# w076oAsBuilt.net
KiCad netlist of a schematic drawn in EAGLE
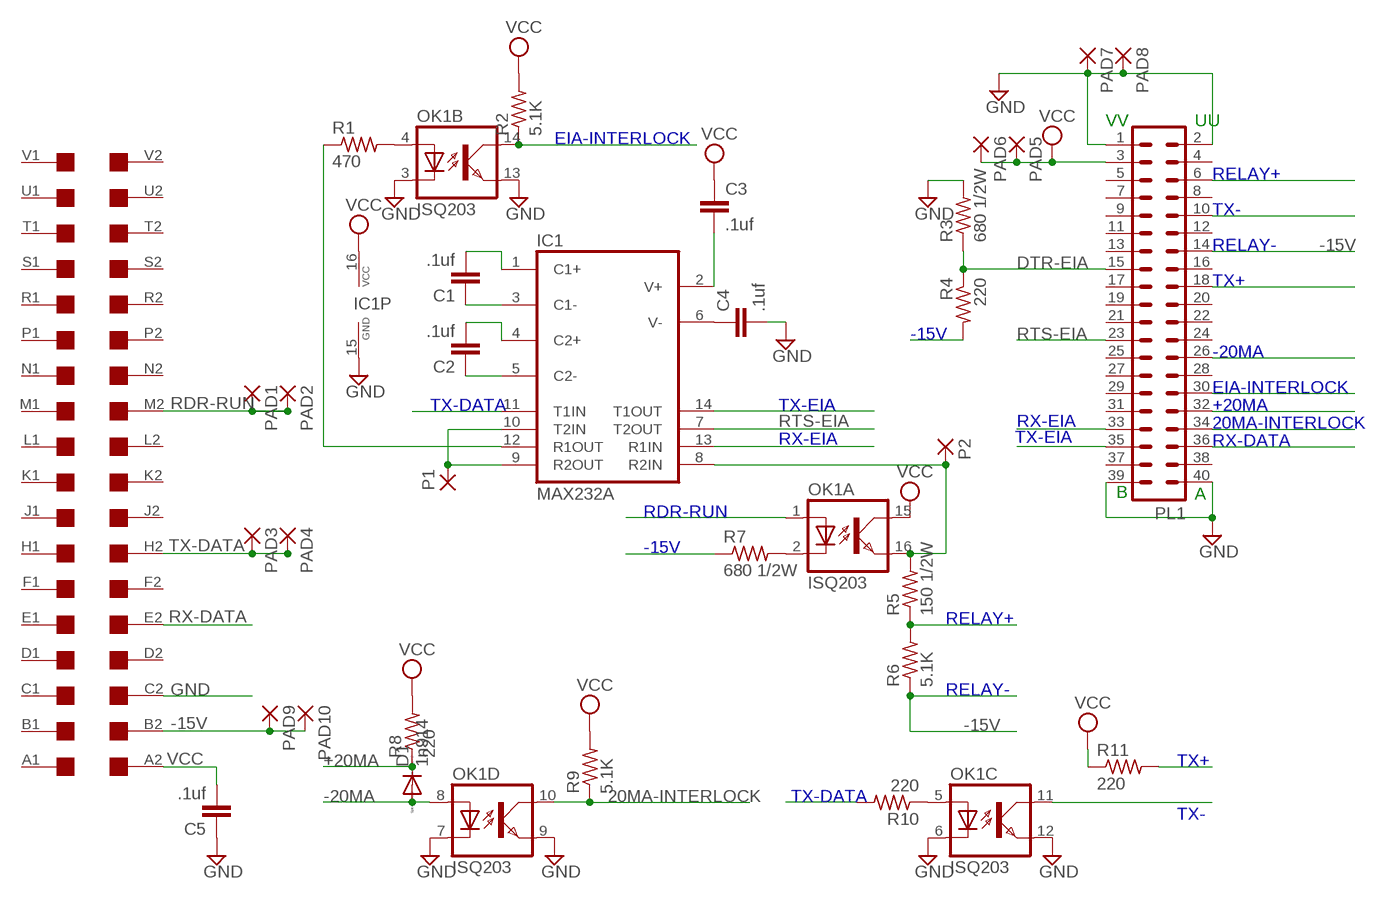
[diagram p0: schematic, sheet 1]

(export (version "E")
  (design (tool "Eeschema 10.0.6"))
  (components
    (comp (ref "C1")
      (value ".1uf")
      (footprint "eagle-import:C050-025X075")
      (libsource (lib "eagle-import") (part "C-EU050-025X075"))
    )
    (comp (ref "C2")
      (value ".1uf")
      (footprint "eagle-import:C050-025X075")
      (libsource (lib "eagle-import") (part "C-EU050-025X075"))
    )
    (comp (ref "C3")
      (value ".1uf")
      (footprint "eagle-import:C050-025X075")
      (libsource (lib "eagle-import") (part "C-EU050-025X075"))
    )
    (comp (ref "C4")
      (value ".1uf")
      (footprint "eagle-import:C050-025X075")
      (libsource (lib "eagle-import") (part "C-EU050-025X075"))
    )
    (comp (ref "C5")
      (value ".1uf")
      (footprint "eagle-import:C050-025X075")
      (libsource (lib "eagle-import") (part "C-EU050-025X075"))
    )
    (comp (ref "D1")
      (value "1n914")
      (footprint "eagle-import:DO41-10")
      (libsource (lib "eagle-import") (part "1N4004"))
    )
    (comp (ref "IC1")
      (value "MAX232A")
      (footprint "eagle-import:DIL16")
      (fields (field (name "MF") "MAXIM") (field (name "MPN") "MAX232ACPE+"))
      (libsource (lib "eagle-import") (part "MAX232"))
    )
    (comp (ref "OK1")
      (value "ISQ203")
      (footprint "eagle-import:DIL16")
      (fields (field (name "MF") "VISHAY/TELEFUNKEN") (field (name "MPN") "ILQ1"))
      (libsource (lib "eagle-import") (part "ILQ1"))
    )
    (comp (ref "P1")
      (value "1,6/0,8")
      (footprint "eagle-import:1,6_0,8")
      (libsource (lib "eagle-import") (part "1,6/0,8"))
    )
    (comp (ref "P2")
      (value "1,6/0,8")
      (footprint "eagle-import:1,6_0,8")
      (libsource (lib "eagle-import") (part "1,6/0,8"))
    )
    (comp (ref "PAD1")
      (value "1,6/0,8")
      (footprint "eagle-import:1,6_0,8")
      (libsource (lib "eagle-import") (part "1,6/0,8"))
    )
    (comp (ref "PAD2")
      (value "1,6/0,8")
      (footprint "eagle-import:1,6_0,8")
      (libsource (lib "eagle-import") (part "1,6/0,8"))
    )
    (comp (ref "PAD3")
      (value "1,6/0,8")
      (footprint "eagle-import:1,6_0,8")
      (libsource (lib "eagle-import") (part "1,6/0,8"))
    )
    (comp (ref "PAD4")
      (value "1,6/0,8")
      (footprint "eagle-import:1,6_0,8")
      (libsource (lib "eagle-import") (part "1,6/0,8"))
    )
    (comp (ref "PAD5")
      (value "1,6/0,8")
      (footprint "eagle-import:1,6_0,8")
      (libsource (lib "eagle-import") (part "1,6/0,8"))
    )
    (comp (ref "PAD6")
      (value "1,6/0,8")
      (footprint "eagle-import:1,6_0,8")
      (libsource (lib "eagle-import") (part "1,6/0,8"))
    )
    (comp (ref "PAD7")
      (value "1,6/0,8")
      (footprint "eagle-import:1,6_0,8")
      (libsource (lib "eagle-import") (part "1,6/0,8"))
    )
    (comp (ref "PAD8")
      (value "1,6/0,8")
      (footprint "eagle-import:1,6_0,8")
      (libsource (lib "eagle-import") (part "1,6/0,8"))
    )
    (comp (ref "PAD9")
      (value "1,6/0,8")
      (footprint "eagle-import:1,6_0,8")
      (libsource (lib "eagle-import") (part "1,6/0,8"))
    )
    (comp (ref "PAD10")
      (value "1,6/0,8")
      (footprint "eagle-import:1,6_0,8")
      (libsource (lib "eagle-import") (part "1,6/0,8"))
    )
    (comp (ref "PL1")
      (value "40H")
      (footprint "eagle-import:40H")
      (libsource (lib "eagle-import") (part "40H"))
    )
    (comp (ref "R1")
      (value "470")
      (footprint "eagle-import:0207_10")
      (libsource (lib "eagle-import") (part "R-US_0207/10"))
    )
    (comp (ref "R2")
      (value "5.1K")
      (footprint "eagle-import:0207_10")
      (libsource (lib "eagle-import") (part "R-US_0207/10"))
    )
    (comp (ref "R3")
      (value "680 1/2W")
      (footprint "eagle-import:0207_12")
      (libsource (lib "eagle-import") (part "R-US_0207/12"))
    )
    (comp (ref "R4")
      (value "220")
      (footprint "eagle-import:0207_10")
      (libsource (lib "eagle-import") (part "R-US_0207/10"))
    )
    (comp (ref "R5")
      (value "150 1/2W")
      (footprint "eagle-import:0207_12")
      (libsource (lib "eagle-import") (part "R-US_0207/12"))
    )
    (comp (ref "R6")
      (value "5.1K")
      (footprint "eagle-import:0207_10")
      (libsource (lib "eagle-import") (part "R-US_0207/10"))
    )
    (comp (ref "R7")
      (value "680 1/2W")
      (footprint "eagle-import:0207_12")
      (libsource (lib "eagle-import") (part "R-US_0207/12"))
    )
    (comp (ref "R8")
      (value "220")
      (footprint "eagle-import:0207_10")
      (libsource (lib "eagle-import") (part "R-US_0207/10"))
    )
    (comp (ref "R9")
      (value "5.1K")
      (footprint "eagle-import:0207_10")
      (libsource (lib "eagle-import") (part "R-US_0207/10"))
    )
    (comp (ref "R10")
      (value "220")
      (footprint "eagle-import:0207_10")
      (libsource (lib "eagle-import") (part "R-US_0207/10"))
    )
    (comp (ref "R11")
      (value "220")
      (footprint "eagle-import:0207_10")
      (libsource (lib "eagle-import") (part "R-US_0207/10"))
    )
    (comp (ref "U$1")
      (value "DEC-FLIPCHIP")
      (footprint "eagle-import:DEC-FLIPCHIP")
      (libsource (lib "eagle-import") (part "DEC-FLIPCHIP"))
    )
  )
  (nets
    (net (code "1") (name "/+20MA") (class "Default")
      (node (ref "D1") (pin "C") (pinfunction "C_C") (pintype "passive"))
      (node (ref "PL1") (pin "32") (pinfunction "32_32") (pintype "passive"))
      (node (ref "R8") (pin "1") (pinfunction "1_1") (pintype "passive"))
    )
    (net (code "2") (name "/-15V") (class "Default")
      (node (ref "PAD10") (pin "1") (pinfunction "P_1") (pintype "passive"))
      (node (ref "PAD9") (pin "1") (pinfunction "P_1") (pintype "passive"))
      (node (ref "PL1") (pin "14") (pinfunction "14_14") (pintype "passive"))
      (node (ref "R4") (pin "2") (pinfunction "2_2") (pintype "passive"))
      (node (ref "R6") (pin "1") (pinfunction "1_1") (pintype "passive"))
      (node (ref "R7") (pin "1") (pinfunction "1_1") (pintype "passive"))
      (node (ref "U$1") (pin "B2") (pinfunction "B2_B2") (pintype "passive"))
    )
    (net (code "3") (name "/-20MA") (class "Default")
      (node (ref "D1") (pin "A") (pinfunction "A_A") (pintype "passive"))
      (node (ref "OK1") (pin "8") (pinfunction "A_8") (pintype "passive"))
      (node (ref "PL1") (pin "26") (pinfunction "26_26") (pintype "passive"))
    )
    (net (code "4") (name "/20MA-INTERLOCK") (class "Default")
      (node (ref "OK1") (pin "10") (pinfunction "COL_10") (pintype "passive"))
      (node (ref "PL1") (pin "34") (pinfunction "34_34") (pintype "passive"))
      (node (ref "R9") (pin "1") (pinfunction "1_1") (pintype "passive"))
    )
    (net (code "5") (name "/DTR-EIA") (class "Default")
      (node (ref "PL1") (pin "15") (pinfunction "15_15") (pintype "passive"))
      (node (ref "R3") (pin "1") (pinfunction "1_1") (pintype "passive"))
      (node (ref "R4") (pin "1") (pinfunction "1_1") (pintype "passive"))
    )
    (net (code "6") (name "/EIA-INTERLOCK") (class "Default")
      (node (ref "OK1") (pin "14") (pinfunction "COL_14") (pintype "passive"))
      (node (ref "PL1") (pin "30") (pinfunction "30_30") (pintype "passive"))
      (node (ref "R2") (pin "1") (pinfunction "1_1") (pintype "passive"))
    )
    (net (code "7") (name "/RDR-RUN") (class "Default")
      (node (ref "OK1") (pin "1") (pinfunction "A_1") (pintype "passive"))
      (node (ref "PAD1") (pin "1") (pinfunction "P_1") (pintype "passive"))
      (node (ref "PAD2") (pin "1") (pinfunction "P_1") (pintype "passive"))
      (node (ref "U$1") (pin "M2") (pinfunction "M2_M2") (pintype "passive"))
    )
    (net (code "8") (name "/RELAY+") (class "Default")
      (node (ref "PL1") (pin "6") (pinfunction "6_6") (pintype "passive"))
      (node (ref "R5") (pin "1") (pinfunction "1_1") (pintype "passive"))
      (node (ref "R6") (pin "2") (pinfunction "2_2") (pintype "passive"))
    )
    (net (code "9") (name "/RTS-EIA") (class "Default")
      (node (ref "IC1") (pin "7") (pinfunction "T2OUT_7") (pintype "output"))
      (node (ref "PL1") (pin "23") (pinfunction "23_23") (pintype "passive"))
    )
    (net (code "10") (name "/RX-DATA") (class "Default")
      (node (ref "PL1") (pin "36") (pinfunction "36_36") (pintype "passive"))
      (node (ref "U$1") (pin "E2") (pinfunction "E2_E2") (pintype "passive"))
    )
    (net (code "11") (name "/RX-EIA") (class "Default")
      (node (ref "IC1") (pin "13") (pinfunction "R1IN_13") (pintype "input"))
      (node (ref "PL1") (pin "33") (pinfunction "33_33") (pintype "passive"))
    )
    (net (code "12") (name "/TX+") (class "Default")
      (node (ref "PL1") (pin "18") (pinfunction "18_18") (pintype "passive"))
      (node (ref "R11") (pin "2") (pinfunction "2_2") (pintype "passive"))
    )
    (net (code "13") (name "/TX-") (class "Default")
      (node (ref "OK1") (pin "11") (pinfunction "COL_11") (pintype "passive"))
      (node (ref "PL1") (pin "10") (pinfunction "10_10") (pintype "passive"))
    )
    (net (code "14") (name "/TX-DATA") (class "Default")
      (node (ref "IC1") (pin "11") (pinfunction "T1IN_11") (pintype "input"))
      (node (ref "PAD3") (pin "1") (pinfunction "P_1") (pintype "passive"))
      (node (ref "PAD4") (pin "1") (pinfunction "P_1") (pintype "passive"))
      (node (ref "R10") (pin "2") (pinfunction "2_2") (pintype "passive"))
      (node (ref "U$1") (pin "H2") (pinfunction "H2_H2") (pintype "passive"))
    )
    (net (code "15") (name "/TX-EIA") (class "Default")
      (node (ref "IC1") (pin "14") (pinfunction "T1OUT_14") (pintype "output"))
      (node (ref "PL1") (pin "35") (pinfunction "35_35") (pintype "passive"))
    )
    (net (code "16") (name "GND") (class "Default")
      (node (ref "C4") (pin "2") (pinfunction "2_2") (pintype "passive"))
      (node (ref "C5") (pin "1") (pinfunction "1_1") (pintype "passive"))
      (node (ref "IC1") (pin "15") (pinfunction "GND_15") (pintype "power_in"))
      (node (ref "OK1") (pin "12") (pinfunction "EMIT_12") (pintype "passive"))
      (node (ref "OK1") (pin "13") (pinfunction "EMIT_13") (pintype "passive"))
      (node (ref "OK1") (pin "3") (pinfunction "C_3") (pintype "passive"))
      (node (ref "OK1") (pin "6") (pinfunction "C_6") (pintype "passive"))
      (node (ref "OK1") (pin "7") (pinfunction "C_7") (pintype "passive"))
      (node (ref "OK1") (pin "9") (pinfunction "EMIT_9") (pintype "passive"))
      (node (ref "PAD7") (pin "1") (pinfunction "P_1") (pintype "passive"))
      (node (ref "PAD8") (pin "1") (pinfunction "P_1") (pintype "passive"))
      (node (ref "PL1") (pin "1") (pinfunction "1_1") (pintype "passive"))
      (node (ref "PL1") (pin "2") (pinfunction "2_2") (pintype "passive"))
      (node (ref "PL1") (pin "39") (pinfunction "39_39") (pintype "passive"))
      (node (ref "PL1") (pin "40") (pinfunction "40_40") (pintype "passive"))
      (node (ref "R3") (pin "2") (pinfunction "2_2") (pintype "passive"))
      (node (ref "U$1") (pin "C2") (pinfunction "C2_C2") (pintype "passive"))
    )
    (net (code "17") (name "Net-(IC1A-C1+)") (class "Default")
      (node (ref "C1") (pin "2") (pinfunction "2_2") (pintype "passive"))
      (node (ref "IC1") (pin "1") (pinfunction "C1+_1") (pintype "bidirectional"))
    )
    (net (code "18") (name "Net-(IC1A-C1-)") (class "Default")
      (node (ref "C1") (pin "1") (pinfunction "1_1") (pintype "passive"))
      (node (ref "IC1") (pin "3") (pinfunction "C1-_3") (pintype "bidirectional"))
    )
    (net (code "19") (name "Net-(IC1A-C2+)") (class "Default")
      (node (ref "C2") (pin "2") (pinfunction "2_2") (pintype "passive"))
      (node (ref "IC1") (pin "4") (pinfunction "C2+_4") (pintype "bidirectional"))
    )
    (net (code "20") (name "Net-(IC1A-C2-)") (class "Default")
      (node (ref "C2") (pin "1") (pinfunction "1_1") (pintype "passive"))
      (node (ref "IC1") (pin "5") (pinfunction "C2-_5") (pintype "bidirectional"))
    )
    (net (code "21") (name "Net-(IC1A-R1OUT)") (class "Default")
      (node (ref "IC1") (pin "12") (pinfunction "R1OUT_12") (pintype "output"))
      (node (ref "R1") (pin "1") (pinfunction "1_1") (pintype "passive"))
    )
    (net (code "22") (name "Net-(IC1A-R2IN)") (class "Default")
      (node (ref "IC1") (pin "8") (pinfunction "R2IN_8") (pintype "input"))
      (node (ref "OK1") (pin "16") (pinfunction "EMIT_16") (pintype "passive"))
      (node (ref "P2") (pin "1") (pinfunction "P_1") (pintype "passive"))
      (node (ref "R5") (pin "2") (pinfunction "2_2") (pintype "passive"))
    )
    (net (code "23") (name "Net-(IC1A-R2OUT)") (class "Default")
      (node (ref "IC1") (pin "10") (pinfunction "T2IN_10") (pintype "input"))
      (node (ref "IC1") (pin "9") (pinfunction "R2OUT_9") (pintype "output"))
      (node (ref "P1") (pin "1") (pinfunction "P_1") (pintype "passive"))
    )
    (net (code "24") (name "Net-(IC1A-V+)") (class "Default")
      (node (ref "C3") (pin "2") (pinfunction "2_2") (pintype "passive"))
      (node (ref "IC1") (pin "2") (pinfunction "V+_2") (pintype "bidirectional"))
    )
    (net (code "25") (name "Net-(IC1A-V-)") (class "Default")
      (node (ref "C4") (pin "1") (pinfunction "1_1") (pintype "passive"))
      (node (ref "IC1") (pin "6") (pinfunction "V-_6") (pintype "bidirectional"))
    )
    (net (code "26") (name "Net-(OK1A-C)") (class "Default")
      (node (ref "OK1") (pin "2") (pinfunction "C_2") (pintype "passive"))
      (node (ref "R7") (pin "2") (pinfunction "2_2") (pintype "passive"))
    )
    (net (code "27") (name "Net-(OK1B-A)") (class "Default")
      (node (ref "OK1") (pin "4") (pinfunction "A_4") (pintype "passive"))
      (node (ref "R1") (pin "2") (pinfunction "2_2") (pintype "passive"))
    )
    (net (code "28") (name "Net-(OK1C-A)") (class "Default")
      (node (ref "OK1") (pin "5") (pinfunction "A_5") (pintype "passive"))
      (node (ref "R10") (pin "1") (pinfunction "1_1") (pintype "passive"))
    )
    (net (code "29") (name "VCC") (class "Default")
      (node (ref "C3") (pin "1") (pinfunction "1_1") (pintype "passive"))
      (node (ref "C5") (pin "2") (pinfunction "2_2") (pintype "passive"))
      (node (ref "IC1") (pin "16") (pinfunction "VCC_16") (pintype "power_in"))
      (node (ref "OK1") (pin "15") (pinfunction "COL_15") (pintype "passive"))
      (node (ref "PAD5") (pin "1") (pinfunction "P_1") (pintype "passive"))
      (node (ref "PAD6") (pin "1") (pinfunction "P_1") (pintype "passive"))
      (node (ref "PL1") (pin "3") (pinfunction "3_3") (pintype "passive"))
      (node (ref "R11") (pin "1") (pinfunction "1_1") (pintype "passive"))
      (node (ref "R2") (pin "2") (pinfunction "2_2") (pintype "passive"))
      (node (ref "R8") (pin "2") (pinfunction "2_2") (pintype "passive"))
      (node (ref "R9") (pin "2") (pinfunction "2_2") (pintype "passive"))
      (node (ref "U$1") (pin "A2") (pinfunction "A2_A2") (pintype "passive"))
    )
    (net (code "30") (name "unconnected-(PL1-Pad4)") (class "Default")
      (node (ref "PL1") (pin "4") (pinfunction "4_4") (pintype "passive"))
    )
    (net (code "31") (name "unconnected-(PL1-Pad5)") (class "Default")
      (node (ref "PL1") (pin "5") (pinfunction "5_5") (pintype "passive"))
    )
    (net (code "32") (name "unconnected-(PL1-Pad7)") (class "Default")
      (node (ref "PL1") (pin "7") (pinfunction "7_7") (pintype "passive"))
    )
    (net (code "33") (name "unconnected-(PL1-Pad8)") (class "Default")
      (node (ref "PL1") (pin "8") (pinfunction "8_8") (pintype "passive"))
    )
    (net (code "34") (name "unconnected-(PL1-Pad9)") (class "Default")
      (node (ref "PL1") (pin "9") (pinfunction "9_9") (pintype "passive"))
    )
    (net (code "35") (name "unconnected-(PL1-Pad11)") (class "Default")
      (node (ref "PL1") (pin "11") (pinfunction "11_11") (pintype "passive"))
    )
    (net (code "36") (name "unconnected-(PL1-Pad12)") (class "Default")
      (node (ref "PL1") (pin "12") (pinfunction "12_12") (pintype "passive"))
    )
    (net (code "37") (name "unconnected-(PL1-Pad13)") (class "Default")
      (node (ref "PL1") (pin "13") (pinfunction "13_13") (pintype "passive"))
    )
    (net (code "38") (name "unconnected-(PL1-Pad16)") (class "Default")
      (node (ref "PL1") (pin "16") (pinfunction "16_16") (pintype "passive"))
    )
    (net (code "39") (name "unconnected-(PL1-Pad17)") (class "Default")
      (node (ref "PL1") (pin "17") (pinfunction "17_17") (pintype "passive"))
    )
    (net (code "40") (name "unconnected-(PL1-Pad19)") (class "Default")
      (node (ref "PL1") (pin "19") (pinfunction "19_19") (pintype "passive"))
    )
    (net (code "41") (name "unconnected-(PL1-Pad20)") (class "Default")
      (node (ref "PL1") (pin "20") (pinfunction "20_20") (pintype "passive"))
    )
    (net (code "42") (name "unconnected-(PL1-Pad21)") (class "Default")
      (node (ref "PL1") (pin "21") (pinfunction "21_21") (pintype "passive"))
    )
    (net (code "43") (name "unconnected-(PL1-Pad22)") (class "Default")
      (node (ref "PL1") (pin "22") (pinfunction "22_22") (pintype "passive"))
    )
    (net (code "44") (name "unconnected-(PL1-Pad24)") (class "Default")
      (node (ref "PL1") (pin "24") (pinfunction "24_24") (pintype "passive"))
    )
    (net (code "45") (name "unconnected-(PL1-Pad25)") (class "Default")
      (node (ref "PL1") (pin "25") (pinfunction "25_25") (pintype "passive"))
    )
    (net (code "46") (name "unconnected-(PL1-Pad27)") (class "Default")
      (node (ref "PL1") (pin "27") (pinfunction "27_27") (pintype "passive"))
    )
    (net (code "47") (name "unconnected-(PL1-Pad28)") (class "Default")
      (node (ref "PL1") (pin "28") (pinfunction "28_28") (pintype "passive"))
    )
    (net (code "48") (name "unconnected-(PL1-Pad29)") (class "Default")
      (node (ref "PL1") (pin "29") (pinfunction "29_29") (pintype "passive"))
    )
    (net (code "49") (name "unconnected-(PL1-Pad31)") (class "Default")
      (node (ref "PL1") (pin "31") (pinfunction "31_31") (pintype "passive"))
    )
    (net (code "50") (name "unconnected-(PL1-Pad37)") (class "Default")
      (node (ref "PL1") (pin "37") (pinfunction "37_37") (pintype "passive"))
    )
    (net (code "51") (name "unconnected-(PL1-Pad38)") (class "Default")
      (node (ref "PL1") (pin "38") (pinfunction "38_38") (pintype "passive"))
    )
    (net (code "52") (name "unconnected-(U$1-PadA1)") (class "Default")
      (node (ref "U$1") (pin "A1") (pinfunction "A1_A1") (pintype "passive"))
    )
    (net (code "53") (name "unconnected-(U$1-PadB1)") (class "Default")
      (node (ref "U$1") (pin "B1") (pinfunction "B1_B1") (pintype "passive"))
    )
    (net (code "54") (name "unconnected-(U$1-PadC1)") (class "Default")
      (node (ref "U$1") (pin "C1") (pinfunction "C1_C1") (pintype "passive"))
    )
    (net (code "55") (name "unconnected-(U$1-PadD1)") (class "Default")
      (node (ref "U$1") (pin "D1") (pinfunction "D1_D1") (pintype "passive"))
    )
    (net (code "56") (name "unconnected-(U$1-PadD2)") (class "Default")
      (node (ref "U$1") (pin "D2") (pinfunction "D2_D2") (pintype "passive"))
    )
    (net (code "57") (name "unconnected-(U$1-PadE1)") (class "Default")
      (node (ref "U$1") (pin "E1") (pinfunction "E1_E1") (pintype "passive"))
    )
    (net (code "58") (name "unconnected-(U$1-PadF1)") (class "Default")
      (node (ref "U$1") (pin "F1") (pinfunction "F1_F1") (pintype "passive"))
    )
    (net (code "59") (name "unconnected-(U$1-PadF2)") (class "Default")
      (node (ref "U$1") (pin "F2") (pinfunction "F2_F2") (pintype "passive"))
    )
    (net (code "60") (name "unconnected-(U$1-PadH1)") (class "Default")
      (node (ref "U$1") (pin "H1") (pinfunction "H1_H1") (pintype "passive"))
    )
    (net (code "61") (name "unconnected-(U$1-PadJ1)") (class "Default")
      (node (ref "U$1") (pin "J1") (pinfunction "J1_J1") (pintype "passive"))
    )
    (net (code "62") (name "unconnected-(U$1-PadJ2)") (class "Default")
      (node (ref "U$1") (pin "J2") (pinfunction "J2_J2") (pintype "passive"))
    )
    (net (code "63") (name "unconnected-(U$1-PadK1)") (class "Default")
      (node (ref "U$1") (pin "K1") (pinfunction "K1_K1") (pintype "passive"))
    )
    (net (code "64") (name "unconnected-(U$1-PadK2)") (class "Default")
      (node (ref "U$1") (pin "K2") (pinfunction "K2_K2") (pintype "passive"))
    )
    (net (code "65") (name "unconnected-(U$1-PadL1)") (class "Default")
      (node (ref "U$1") (pin "L1") (pinfunction "L1_L1") (pintype "passive"))
    )
    (net (code "66") (name "unconnected-(U$1-PadL2)") (class "Default")
      (node (ref "U$1") (pin "L2") (pinfunction "L2_L2") (pintype "passive"))
    )
    (net (code "67") (name "unconnected-(U$1-PadM1)") (class "Default")
      (node (ref "U$1") (pin "M1") (pinfunction "M1_M1") (pintype "passive"))
    )
    (net (code "68") (name "unconnected-(U$1-PadN1)") (class "Default")
      (node (ref "U$1") (pin "N1") (pinfunction "N1_N1") (pintype "passive"))
    )
    (net (code "69") (name "unconnected-(U$1-PadN2)") (class "Default")
      (node (ref "U$1") (pin "N2") (pinfunction "N2_N2") (pintype "passive"))
    )
    (net (code "70") (name "unconnected-(U$1-PadP1)") (class "Default")
      (node (ref "U$1") (pin "P1") (pinfunction "P1_P1") (pintype "passive"))
    )
    (net (code "71") (name "unconnected-(U$1-PadP2)") (class "Default")
      (node (ref "U$1") (pin "P2") (pinfunction "P2_P2") (pintype "passive"))
    )
    (net (code "72") (name "unconnected-(U$1-PadR1)") (class "Default")
      (node (ref "U$1") (pin "R1") (pinfunction "R1_R1") (pintype "passive"))
    )
    (net (code "73") (name "unconnected-(U$1-PadR2)") (class "Default")
      (node (ref "U$1") (pin "R2") (pinfunction "R2_R2") (pintype "passive"))
    )
    (net (code "74") (name "unconnected-(U$1-PadS1)") (class "Default")
      (node (ref "U$1") (pin "S1") (pinfunction "S1_S1") (pintype "passive"))
    )
    (net (code "75") (name "unconnected-(U$1-PadS2)") (class "Default")
      (node (ref "U$1") (pin "S2") (pinfunction "S2_S2") (pintype "passive"))
    )
    (net (code "76") (name "unconnected-(U$1-PadT1)") (class "Default")
      (node (ref "U$1") (pin "T1") (pinfunction "T1_T1") (pintype "passive"))
    )
    (net (code "77") (name "unconnected-(U$1-PadT2)") (class "Default")
      (node (ref "U$1") (pin "T2") (pinfunction "T2_T2") (pintype "passive"))
    )
    (net (code "78") (name "unconnected-(U$1-PadU1)") (class "Default")
      (node (ref "U$1") (pin "U1") (pinfunction "U1_U1") (pintype "passive"))
    )
    (net (code "79") (name "unconnected-(U$1-PadU2)") (class "Default")
      (node (ref "U$1") (pin "U2") (pinfunction "U2_U2") (pintype "passive"))
    )
    (net (code "80") (name "unconnected-(U$1-PadV1)") (class "Default")
      (node (ref "U$1") (pin "V1") (pinfunction "V1_V1") (pintype "passive"))
    )
    (net (code "81") (name "unconnected-(U$1-PadV2)") (class "Default")
      (node (ref "U$1") (pin "V2") (pinfunction "V2_V2") (pintype "passive"))
    )
  )
)
